# USB.net
KiCad netlist of a schematic drawn in Altium Designer
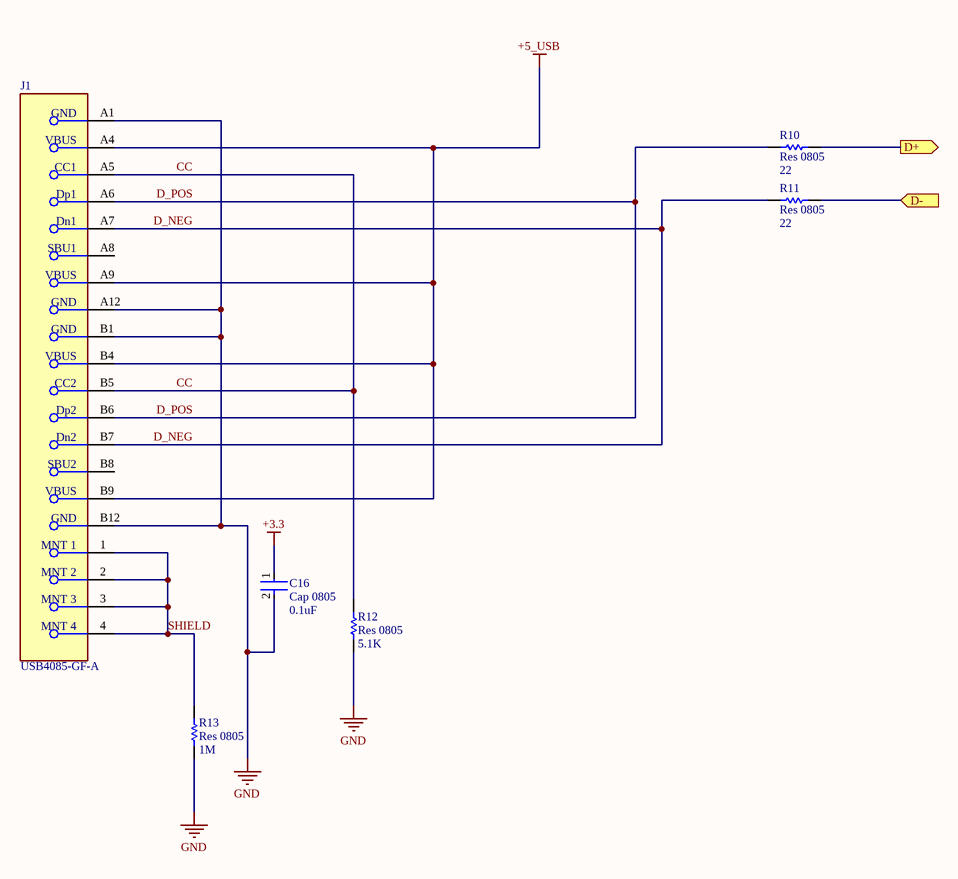
[diagram p0: USB.SchDoc]

(export (version "E")
  (design (tool "Eeschema 10.0.6"))
  (components
    (comp (ref "C16")
      (value "Cap 0805")
      (footprint "FP-GRM216-0_1-IPC_C")
      (description "Capacitor")
      (fields (field (name "ALTIUM_VALUE") "0.1uF"))
      (libsource (lib "Altium Content Vault") (part "236180d848d6139a670b325ea6854c9"))
    )
    (comp (ref "J1")
      (value "USB4085-GF-A")
      (footprint "FP-USB4085-GF-A-MFG")
      (description "CONN RCPT USB2.0 TYPEC 16POS")
      (fields
        (field (name "MANUFACTURER") "Global Connector Technology")
        (field (name "OCTOPART") "https://octopart.com/usb4085-gf-a-global+connector+technology-94773699")
      )
      (libsource (lib "Altium Content Vault") (part "f6997dba88850a18107ac0013977506"))
    )
    (comp (ref "R10")
      (value "Res 0805")
      (footprint "RESC2013X50X30LL20T20")
      (description "Resistor")
      (fields (field (name "ALTIUM_VALUE") "22"))
      (libsource (lib "Altium Content Vault") (part "RES"))
    )
    (comp (ref "R11")
      (value "Res 0805")
      (footprint "RESC2013X50X30LL20T20")
      (description "Resistor")
      (fields (field (name "ALTIUM_VALUE") "22"))
      (libsource (lib "Altium Content Vault") (part "RES"))
    )
    (comp (ref "R12")
      (value "Res 0805")
      (footprint "RESC2013X50X30LL20T20")
      (description "Resistor")
      (fields (field (name "ALTIUM_VALUE") "5.1K"))
      (libsource (lib "Altium Content Vault") (part "RES"))
    )
    (comp (ref "R13")
      (value "Res 0805")
      (footprint "RESC2013X50X30LL20T20")
      (description "Resistor")
      (fields (field (name "ALTIUM_VALUE") "1M"))
      (libsource (lib "Altium Content Vault") (part "RES"))
    )
  )
  (nets
    (net (code "1") (name "+3.3") (class "Default")
      (node (ref "C16") (pin "1") (pinfunction "1_1") (pintype "passive"))
    )
    (net (code "2") (name "+5_USB") (class "Default")
      (node (ref "J1") (pin "A4") (pinfunction "VBUS_A4") (pintype "power_in"))
      (node (ref "J1") (pin "A9") (pinfunction "VBUS_A9") (pintype "power_in"))
      (node (ref "J1") (pin "B4") (pinfunction "VBUS_B4") (pintype "power_in"))
      (node (ref "J1") (pin "B9") (pinfunction "VBUS_B9") (pintype "power_in"))
    )
    (net (code "3") (name "/CC") (class "Default")
      (node (ref "J1") (pin "A5") (pinfunction "CC1_A5") (pintype "passive"))
      (node (ref "J1") (pin "B5") (pinfunction "CC2_B5") (pintype "passive"))
      (node (ref "R12") (pin "1") (pinfunction "1_1") (pintype "passive"))
    )
    (net (code "4") (name "/D+") (class "Default")
      (node (ref "R10") (pin "1") (pinfunction "1_1") (pintype "passive"))
    )
    (net (code "5") (name "/D-") (class "Default")
      (node (ref "R11") (pin "1") (pinfunction "1_1") (pintype "passive"))
    )
    (net (code "6") (name "/D_NEG") (class "Default")
      (node (ref "J1") (pin "A7") (pinfunction "Dn1_A7") (pintype "passive"))
      (node (ref "J1") (pin "B7") (pinfunction "Dn2_B7") (pintype "passive"))
      (node (ref "R11") (pin "2") (pinfunction "2_2") (pintype "passive"))
    )
    (net (code "7") (name "/D_POS") (class "Default")
      (node (ref "J1") (pin "A6") (pinfunction "Dp1_A6") (pintype "passive"))
      (node (ref "J1") (pin "B6") (pinfunction "Dp2_B6") (pintype "passive"))
      (node (ref "R10") (pin "2") (pinfunction "2_2") (pintype "passive"))
    )
    (net (code "8") (name "/SHIELD") (class "Default")
      (node (ref "J1") (pin "1") (pinfunction "MNT_1_1") (pintype "passive"))
      (node (ref "J1") (pin "2") (pinfunction "MNT_2_2") (pintype "passive"))
      (node (ref "J1") (pin "3") (pinfunction "MNT_3_3") (pintype "passive"))
      (node (ref "J1") (pin "4") (pinfunction "MNT_4_4") (pintype "passive"))
      (node (ref "R13") (pin "1") (pinfunction "1_1") (pintype "passive"))
    )
    (net (code "9") (name "GND") (class "Default")
      (node (ref "C16") (pin "2") (pinfunction "2_2") (pintype "passive"))
      (node (ref "J1") (pin "A1") (pinfunction "GND_A1") (pintype "power_in"))
      (node (ref "J1") (pin "A12") (pinfunction "GND_A12") (pintype "power_in"))
      (node (ref "J1") (pin "B1") (pinfunction "GND_B1") (pintype "power_in"))
      (node (ref "J1") (pin "B12") (pinfunction "GND_B12") (pintype "power_in"))
      (node (ref "R12") (pin "2") (pinfunction "2_2") (pintype "passive"))
      (node (ref "R13") (pin "2") (pinfunction "2_2") (pintype "passive"))
    )
    (net (code "10") (name "unconnected-(J1-SBU1-PadA8)") (class "Default")
      (node (ref "J1") (pin "A8") (pinfunction "SBU1_A8") (pintype "passive"))
    )
    (net (code "11") (name "unconnected-(J1-SBU2-PadB8)") (class "Default")
      (node (ref "J1") (pin "B8") (pinfunction "SBU2_B8") (pintype "passive"))
    )
  )
)
